# LVDS.net
KiCad netlist of a schematic drawn in Altium Designer
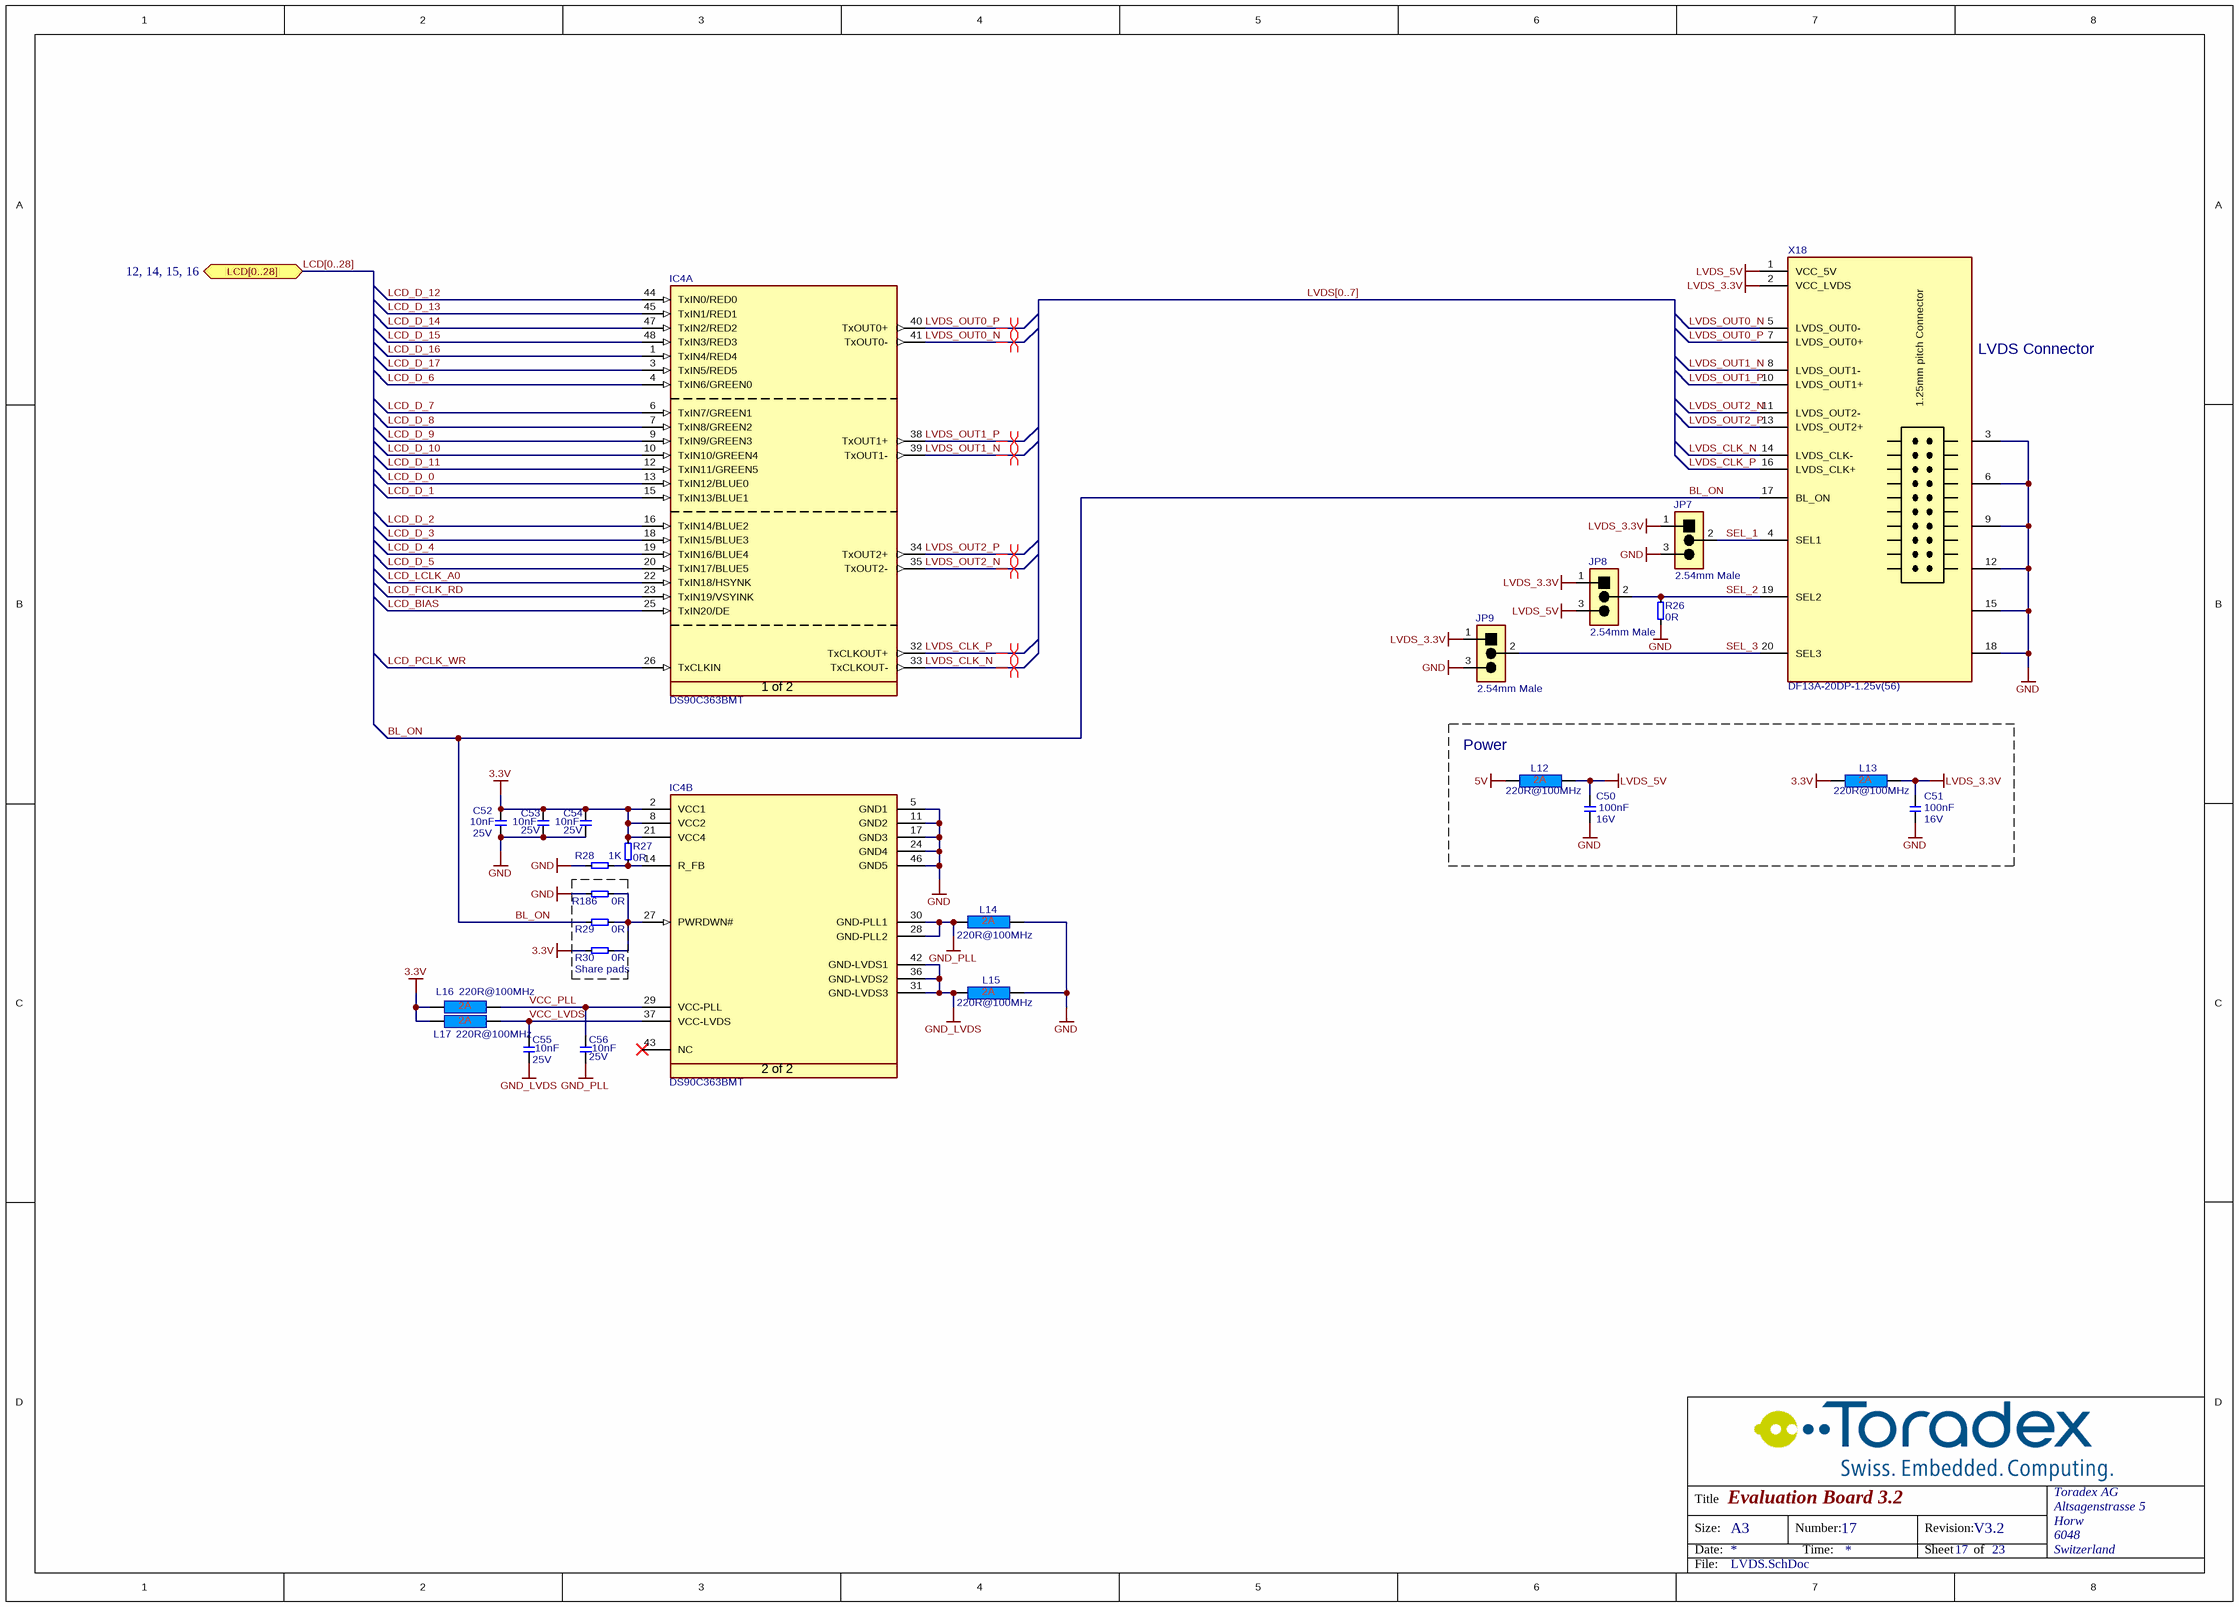
[diagram p0: LVDS.SchDoc]

(export (version "E")
  (design (tool "Eeschema 10.0.6"))
  (components
    (comp (ref "C50")
      (value "100nF")
      (footprint "T_CAPC0603X33N")
      (description "Capacitor Ceramic X7R 100nF 16V 10% 0603")
      (fields (field (name "TOLERANCE") "10%") (field (name "RATING") "16V"))
      (libsource (lib "Evaluation Board") (part "C-X7R-100nF-16V-10%-0603"))
    )
    (comp (ref "C51")
      (value "100nF")
      (footprint "T_CAPC0603X33N")
      (description "Capacitor Ceramic X7R 100nF 16V 10% 0603")
      (fields (field (name "TOLERANCE") "10%") (field (name "RATING") "16V"))
      (libsource (lib "Evaluation Board") (part "C-X7R-100nF-16V-10%-0603"))
    )
    (comp (ref "C52")
      (value "10nF")
      (footprint "T_CAPC0603X33N")
      (description "Capacitor Ceramic X7R 10nF 25V 10% 0603")
      (fields (field (name "TOLERANCE") "10%") (field (name "RATING") "25V"))
      (libsource (lib "Evaluation Board") (part "C-X7R-10nF-25V-10%-0603"))
    )
    (comp (ref "C53")
      (value "10nF")
      (footprint "T_CAPC0603X33N")
      (description "Capacitor Ceramic X7R 10nF 25V 10% 0603")
      (fields (field (name "TOLERANCE") "10%") (field (name "RATING") "25V"))
      (libsource (lib "Evaluation Board") (part "C-X7R-10nF-25V-10%-0603"))
    )
    (comp (ref "C54")
      (value "10nF")
      (footprint "T_CAPC0603X33N")
      (description "Capacitor Ceramic X7R 10nF 25V 10% 0603")
      (fields (field (name "TOLERANCE") "10%") (field (name "RATING") "25V"))
      (libsource (lib "Evaluation Board") (part "C-X7R-10nF-25V-10%-0603"))
    )
    (comp (ref "C55")
      (value "10nF")
      (footprint "T_CAPC0603X33N")
      (description "Capacitor Ceramic X7R 10nF 25V 10% 0603")
      (fields (field (name "TOLERANCE") "10%") (field (name "RATING") "25V"))
      (libsource (lib "Evaluation Board") (part "C-X7R-10nF-25V-10%-0603"))
    )
    (comp (ref "C56")
      (value "10nF")
      (footprint "T_CAPC0603X33N")
      (description "Capacitor Ceramic X7R 10nF 25V 10% 0603")
      (fields (field (name "TOLERANCE") "10%") (field (name "RATING") "25V"))
      (libsource (lib "Evaluation Board") (part "C-X7R-10nF-25V-10%-0603"))
    )
    (comp (ref "IC4")
      (value "DS90C363BMT")
      (footprint "SOP50P810X120-48N")
      (description "LVDS Converter")
      (fields (field (name "MANUFACTURER PART NO.") "DS90C363BMT"))
      (libsource (lib "Evaluation Board") (part "IC-NS-DS90C363BMT"))
    )
    (comp (ref "JP7")
      (value "826936-3")
      (footprint "T_TYCO_826936-3")
      (description "Jumper, 3-Pin")
      (libsource (lib "Evaluation Board") (part "CON-Tyco-826936-3-1X3-2.54mm-JP"))
    )
    (comp (ref "JP8")
      (value "826936-3")
      (footprint "T_TYCO_826936-3")
      (description "Jumper, 3-Pin")
      (libsource (lib "Evaluation Board") (part "CON-Tyco-826936-3-1X3-2.54mm-JP"))
    )
    (comp (ref "JP9")
      (value "826936-3")
      (footprint "T_TYCO_826936-3")
      (description "Jumper, 3-Pin")
      (libsource (lib "Evaluation Board") (part "CON-Tyco-826936-3-1X3-2.54mm-JP"))
    )
    (comp (ref "L12")
      (value "220R@100MHz")
      (footprint "INDC1608X95N")
      (description "220R@100MHz 2A EMI FILTER")
      (fields (field (name "TOLERANCE") "25%"))
      (libsource (lib "Evaluation Board") (part "L-220R@100MHz-2A-25%-0603"))
    )
    (comp (ref "L13")
      (value "220R@100MHz")
      (footprint "INDC1608X95N")
      (description "220R@100MHz 2A EMI FILTER")
      (fields (field (name "TOLERANCE") "25%"))
      (libsource (lib "Evaluation Board") (part "L-220R@100MHz-2A-25%-0603"))
    )
    (comp (ref "L14")
      (value "220R@100MHz")
      (footprint "INDC1608X95N")
      (description "220R@100MHz 2A EMI FILTER")
      (fields (field (name "TOLERANCE") "25%"))
      (libsource (lib "Evaluation Board") (part "L-220R@100MHz-2A-25%-0603"))
    )
    (comp (ref "L15")
      (value "220R@100MHz")
      (footprint "INDC1608X95N")
      (description "220R@100MHz 2A EMI FILTER")
      (fields (field (name "TOLERANCE") "25%"))
      (libsource (lib "Evaluation Board") (part "L-220R@100MHz-2A-25%-0603"))
    )
    (comp (ref "L16")
      (value "220R@100MHz")
      (footprint "INDC1608X95N")
      (description "220R@100MHz 2A EMI FILTER")
      (fields (field (name "TOLERANCE") "25%"))
      (libsource (lib "Evaluation Board") (part "L-220R@100MHz-2A-25%-0603"))
    )
    (comp (ref "L17")
      (value "220R@100MHz")
      (footprint "INDC1608X95N")
      (description "220R@100MHz 2A EMI FILTER")
      (fields (field (name "TOLERANCE") "25%"))
      (libsource (lib "Evaluation Board") (part "L-220R@100MHz-2A-25%-0603"))
    )
    (comp (ref "R26")
      (value "0R")
      (footprint "t_RESC0603X30N")
      (description "Resistor 0 ohm 63mW 1% 0603")
      (fields (field (name "TOLERANCE") "1%"))
      (libsource (lib "Evaluation Board") (part "R-0R-63mW-1%-0603"))
    )
    (comp (ref "R27")
      (value "0R")
      (footprint "t_RESC0603X30N")
      (description "Resistor 0 ohm 63mW 1% 0603")
      (fields (field (name "TOLERANCE") "1%"))
      (libsource (lib "Evaluation Board") (part "R-0R-63mW-1%-0603"))
    )
    (comp (ref "R28")
      (value "1K")
      (footprint "t_RESC0603X30N")
      (description "Resistor 1 Kohm 63mW 5% 0603")
      (fields (field (name "TOLERANCE") "5%"))
      (libsource (lib "Evaluation Board") (part "R-1KR-63mW-5%-0603"))
    )
    (comp (ref "R29")
      (value "0R")
      (footprint "t_RESC0603X30N")
      (description "Resistor 0 ohm 63mW 1% 0603")
      (fields (field (name "TOLERANCE") "1%"))
      (libsource (lib "Evaluation Board") (part "R-0R-63mW-1%-0603"))
    )
    (comp (ref "R30")
      (value "0R")
      (footprint "t_RESC0603X30N")
      (description "Resistor 0 ohm 63mW 1% 0603")
      (fields (field (name "TOLERANCE") "1%"))
      (libsource (lib "Evaluation Board") (part "R-0R-63mW-1%-0603"))
    )
    (comp (ref "R186")
      (value "0R")
      (footprint "t_RESC0603X30N")
      (description "Resistor 0 ohm 63mW 1% 0603")
      (fields (field (name "TOLERANCE") "1%"))
      (libsource (lib "Evaluation Board") (part "R-0R-63mW-1%-0603"))
    )
    (comp (ref "X18")
      (value "CON-Hirose-DF13A-20DP-1.25v(56)-2x10-1mm")
      (footprint "T_HIROSE_DF13A-20DP-1.25V(56)")
      (description "LVDS Connector")
      (fields (field (name "MANUFACTURER PART NO.") "DF13A-20DP-1.25v(56)"))
      (libsource (lib "Evaluation Board") (part "CON-Hirose-DF13A-20DP-1.25v(56)-2x10-1mm"))
    )
  )
  (nets
    (net (code "38") (name "/BL_ON") (class "Default")
      (node (ref "R29") (pin "1") (pinfunction "1_1") (pintype "passive"))
      (node (ref "X18") (pin "17") (pinfunction "BL_ON_17") (pintype "passive"))
    )
    (net (code "40") (name "/LCD_BIAS") (class "Default")
      (node (ref "IC4") (pin "25") (pinfunction "TxIN20/DE_25") (pintype "input"))
    )
    (net (code "41") (name "/LCD_D_0") (class "Default")
      (node (ref "IC4") (pin "13") (pinfunction "TxIN12/BLUE0_13") (pintype "input"))
    )
    (net (code "42") (name "/LCD_D_1") (class "Default")
      (node (ref "IC4") (pin "15") (pinfunction "TxIN13/BLUE1_15") (pintype "input"))
    )
    (net (code "43") (name "/LCD_D_2") (class "Default")
      (node (ref "IC4") (pin "16") (pinfunction "TxIN14/BLUE2_16") (pintype "input"))
    )
    (net (code "44") (name "/LCD_D_3") (class "Default")
      (node (ref "IC4") (pin "18") (pinfunction "TxIN15/BLUE3_18") (pintype "input"))
    )
    (net (code "45") (name "/LCD_D_4") (class "Default")
      (node (ref "IC4") (pin "19") (pinfunction "TxIN16/BLUE4_19") (pintype "input"))
    )
    (net (code "46") (name "/LCD_D_5") (class "Default")
      (node (ref "IC4") (pin "20") (pinfunction "TxIN17/BLUE5_20") (pintype "input"))
    )
    (net (code "47") (name "/LCD_D_6") (class "Default")
      (node (ref "IC4") (pin "4") (pinfunction "TxIN6/GREEN0_4") (pintype "input"))
    )
    (net (code "48") (name "/LCD_D_7") (class "Default")
      (node (ref "IC4") (pin "6") (pinfunction "TxIN7/GREEN1_6") (pintype "input"))
    )
    (net (code "49") (name "/LCD_D_8") (class "Default")
      (node (ref "IC4") (pin "7") (pinfunction "TxIN8/GREEN2_7") (pintype "input"))
    )
    (net (code "50") (name "/LCD_D_9") (class "Default")
      (node (ref "IC4") (pin "9") (pinfunction "TxIN9/GREEN3_9") (pintype "input"))
    )
    (net (code "51") (name "/LCD_D_10") (class "Default")
      (node (ref "IC4") (pin "10") (pinfunction "TxIN10/GREEN4_10") (pintype "input"))
    )
    (net (code "52") (name "/LCD_D_11") (class "Default")
      (node (ref "IC4") (pin "12") (pinfunction "TxIN11/GREEN5_12") (pintype "input"))
    )
    (net (code "53") (name "/LCD_D_12") (class "Default")
      (node (ref "IC4") (pin "44") (pinfunction "TxIN0/RED0_44") (pintype "input"))
    )
    (net (code "54") (name "/LCD_D_13") (class "Default")
      (node (ref "IC4") (pin "45") (pinfunction "TxIN1/RED1_45") (pintype "input"))
    )
    (net (code "55") (name "/LCD_D_14") (class "Default")
      (node (ref "IC4") (pin "47") (pinfunction "TxIN2/RED2_47") (pintype "input"))
    )
    (net (code "56") (name "/LCD_D_15") (class "Default")
      (node (ref "IC4") (pin "48") (pinfunction "TxIN3/RED3_48") (pintype "input"))
    )
    (net (code "57") (name "/LCD_D_16") (class "Default")
      (node (ref "IC4") (pin "1") (pinfunction "TxIN4/RED4_1") (pintype "input"))
    )
    (net (code "58") (name "/LCD_D_17") (class "Default")
      (node (ref "IC4") (pin "3") (pinfunction "TxIN5/RED5_3") (pintype "input"))
    )
    (net (code "59") (name "/LCD_FCLK_RD") (class "Default")
      (node (ref "IC4") (pin "23") (pinfunction "TxIN19/VSYINK_23") (pintype "input"))
    )
    (net (code "60") (name "/LCD_LCLK_A0") (class "Default")
      (node (ref "IC4") (pin "22") (pinfunction "TxIN18/HSYNK_22") (pintype "input"))
    )
    (net (code "61") (name "/LCD_PCLK_WR") (class "Default")
      (node (ref "IC4") (pin "26") (pinfunction "TxCLKIN_26") (pintype "input"))
    )
    (net (code "63") (name "/LVDS_CLK_N") (class "Default")
      (node (ref "IC4") (pin "33") (pinfunction "TxCLKOUT-_33") (pintype "output"))
      (node (ref "X18") (pin "14") (pinfunction "LVDS_CLK-_14") (pintype "passive"))
    )
    (net (code "64") (name "/LVDS_CLK_P") (class "Default")
      (node (ref "IC4") (pin "32") (pinfunction "TxCLKOUT+_32") (pintype "output"))
      (node (ref "X18") (pin "16") (pinfunction "LVDS_CLK+_16") (pintype "passive"))
    )
    (net (code "65") (name "/LVDS_OUT0_N") (class "Default")
      (node (ref "IC4") (pin "41") (pinfunction "TxOUT0-_41") (pintype "output"))
      (node (ref "X18") (pin "5") (pinfunction "LVDS_OUT0-_5") (pintype "passive"))
    )
    (net (code "66") (name "/LVDS_OUT0_P") (class "Default")
      (node (ref "IC4") (pin "40") (pinfunction "TxOUT0+_40") (pintype "output"))
      (node (ref "X18") (pin "7") (pinfunction "LVDS_OUT0+_7") (pintype "passive"))
    )
    (net (code "67") (name "/LVDS_OUT1_N") (class "Default")
      (node (ref "IC4") (pin "39") (pinfunction "TxOUT1-_39") (pintype "output"))
      (node (ref "X18") (pin "8") (pinfunction "LVDS_OUT1-_8") (pintype "passive"))
    )
    (net (code "68") (name "/LVDS_OUT1_P") (class "Default")
      (node (ref "IC4") (pin "38") (pinfunction "TxOUT1+_38") (pintype "output"))
      (node (ref "X18") (pin "10") (pinfunction "LVDS_OUT1+_10") (pintype "passive"))
    )
    (net (code "69") (name "/LVDS_OUT2_N") (class "Default")
      (node (ref "IC4") (pin "35") (pinfunction "TxOUT2-_35") (pintype "output"))
      (node (ref "X18") (pin "11") (pinfunction "LVDS_OUT2-_11") (pintype "passive"))
    )
    (net (code "70") (name "/LVDS_OUT2_P") (class "Default")
      (node (ref "IC4") (pin "34") (pinfunction "TxOUT2+_34") (pintype "output"))
      (node (ref "X18") (pin "13") (pinfunction "LVDS_OUT2+_13") (pintype "passive"))
    )
    (net (code "71") (name "/SEL_1") (class "Default")
      (node (ref "JP7") (pin "2") (pinfunction "2_2") (pintype "passive"))
      (node (ref "X18") (pin "4") (pinfunction "SEL1_4") (pintype "passive"))
    )
    (net (code "72") (name "/SEL_2") (class "Default")
      (node (ref "JP8") (pin "2") (pinfunction "2_2") (pintype "passive"))
      (node (ref "R26") (pin "2") (pinfunction "2_2") (pintype "passive"))
      (node (ref "X18") (pin "19") (pinfunction "SEL2_19") (pintype "passive"))
    )
    (net (code "73") (name "/SEL_3") (class "Default")
      (node (ref "JP9") (pin "2") (pinfunction "2_2") (pintype "passive"))
      (node (ref "X18") (pin "20") (pinfunction "SEL3_20") (pintype "passive"))
    )
    (net (code "74") (name "/VCC_LVDS") (class "Default")
      (node (ref "C55") (pin "2") (pinfunction "2_2") (pintype "passive"))
      (node (ref "IC4") (pin "37") (pinfunction "VCC-LVDS_37") (pintype "power_in"))
      (node (ref "L17") (pin "2") (pinfunction "2_2") (pintype "passive"))
    )
    (net (code "75") (name "/VCC_PLL") (class "Default")
      (node (ref "C56") (pin "2") (pinfunction "2_2") (pintype "passive"))
      (node (ref "IC4") (pin "29") (pinfunction "VCC-PLL_29") (pintype "power_in"))
      (node (ref "L16") (pin "2") (pinfunction "2_2") (pintype "passive"))
    )
    (net (code "76") (name "3.3V") (class "Default")
      (node (ref "C52") (pin "2") (pinfunction "2_2") (pintype "passive"))
      (node (ref "C53") (pin "2") (pinfunction "2_2") (pintype "passive"))
      (node (ref "C54") (pin "2") (pinfunction "2_2") (pintype "passive"))
      (node (ref "IC4") (pin "2") (pinfunction "VCC1_2") (pintype "power_in"))
      (node (ref "IC4") (pin "21") (pinfunction "VCC4_21") (pintype "power_in"))
      (node (ref "IC4") (pin "8") (pinfunction "VCC2_8") (pintype "power_in"))
      (node (ref "L13") (pin "1") (pinfunction "1_1") (pintype "passive"))
      (node (ref "L16") (pin "1") (pinfunction "1_1") (pintype "passive"))
      (node (ref "L17") (pin "1") (pinfunction "1_1") (pintype "passive"))
      (node (ref "R27") (pin "2") (pinfunction "2_2") (pintype "passive"))
      (node (ref "R30") (pin "1") (pinfunction "1_1") (pintype "passive"))
    )
    (net (code "77") (name "5V") (class "Default")
      (node (ref "L12") (pin "1") (pinfunction "1_1") (pintype "passive"))
    )
    (net (code "78") (name "GND") (class "Default")
      (node (ref "C50") (pin "1") (pinfunction "1_1") (pintype "passive"))
      (node (ref "C51") (pin "1") (pinfunction "1_1") (pintype "passive"))
      (node (ref "C52") (pin "1") (pinfunction "1_1") (pintype "passive"))
      (node (ref "C53") (pin "1") (pinfunction "1_1") (pintype "passive"))
      (node (ref "C54") (pin "1") (pinfunction "1_1") (pintype "passive"))
      (node (ref "IC4") (pin "11") (pinfunction "GND2_11") (pintype "power_in"))
      (node (ref "IC4") (pin "17") (pinfunction "GND3_17") (pintype "power_in"))
      (node (ref "IC4") (pin "24") (pinfunction "GND4_24") (pintype "power_in"))
      (node (ref "IC4") (pin "46") (pinfunction "GND5_46") (pintype "power_in"))
      (node (ref "IC4") (pin "5") (pinfunction "GND1_5") (pintype "power_in"))
      (node (ref "JP7") (pin "3") (pinfunction "3_3") (pintype "passive"))
      (node (ref "JP9") (pin "3") (pinfunction "3_3") (pintype "passive"))
      (node (ref "L14") (pin "2") (pinfunction "2_2") (pintype "passive"))
      (node (ref "L15") (pin "2") (pinfunction "2_2") (pintype "passive"))
      (node (ref "R186") (pin "1") (pinfunction "1_1") (pintype "passive"))
      (node (ref "R26") (pin "1") (pinfunction "1_1") (pintype "passive"))
      (node (ref "R28") (pin "1") (pinfunction "1_1") (pintype "passive"))
      (node (ref "X18") (pin "12") (pinfunction "GND_12") (pintype "passive"))
      (node (ref "X18") (pin "15") (pinfunction "GND_15") (pintype "passive"))
      (node (ref "X18") (pin "18") (pinfunction "GND_18") (pintype "passive"))
      (node (ref "X18") (pin "3") (pinfunction "GND_3") (pintype "passive"))
      (node (ref "X18") (pin "6") (pinfunction "GND_6") (pintype "passive"))
      (node (ref "X18") (pin "9") (pinfunction "GND_9") (pintype "passive"))
    )
    (net (code "79") (name "GND_LVDS") (class "Default")
      (node (ref "C55") (pin "1") (pinfunction "1_1") (pintype "passive"))
      (node (ref "IC4") (pin "31") (pinfunction "GND-LVDS3_31") (pintype "power_in"))
      (node (ref "IC4") (pin "36") (pinfunction "GND-LVDS2_36") (pintype "power_in"))
      (node (ref "IC4") (pin "42") (pinfunction "GND-LVDS1_42") (pintype "power_in"))
      (node (ref "L15") (pin "1") (pinfunction "1_1") (pintype "passive"))
    )
    (net (code "80") (name "GND_PLL") (class "Default")
      (node (ref "C56") (pin "1") (pinfunction "1_1") (pintype "passive"))
      (node (ref "IC4") (pin "28") (pinfunction "GND-PLL2_28") (pintype "power_in"))
      (node (ref "IC4") (pin "30") (pinfunction "GND-PLL1_30") (pintype "power_in"))
      (node (ref "L14") (pin "1") (pinfunction "1_1") (pintype "passive"))
    )
    (net (code "81") (name "LVDS_3.3V") (class "Default")
      (node (ref "C51") (pin "2") (pinfunction "2_2") (pintype "passive"))
      (node (ref "JP7") (pin "1") (pinfunction "1_1") (pintype "passive"))
      (node (ref "JP8") (pin "1") (pinfunction "1_1") (pintype "passive"))
      (node (ref "JP9") (pin "1") (pinfunction "1_1") (pintype "passive"))
      (node (ref "L13") (pin "2") (pinfunction "2_2") (pintype "passive"))
      (node (ref "X18") (pin "2") (pinfunction "VCC_LVDS_2") (pintype "passive"))
    )
    (net (code "82") (name "LVDS_5V") (class "Default")
      (node (ref "C50") (pin "2") (pinfunction "2_2") (pintype "passive"))
      (node (ref "JP8") (pin "3") (pinfunction "3_3") (pintype "passive"))
      (node (ref "L12") (pin "2") (pinfunction "2_2") (pintype "passive"))
      (node (ref "X18") (pin "1") (pinfunction "VCC_5V_1") (pintype "passive"))
    )
    (net (code "83") (name "Net-(IC4B-PWRDWN#)") (class "Default")
      (node (ref "IC4") (pin "27") (pinfunction "PWRDWN#_27") (pintype "input"))
      (node (ref "R186") (pin "2") (pinfunction "2_2") (pintype "passive"))
      (node (ref "R29") (pin "2") (pinfunction "2_2") (pintype "passive"))
      (node (ref "R30") (pin "2") (pinfunction "2_2") (pintype "passive"))
    )
    (net (code "84") (name "Net-(IC4B-R_FB)") (class "Default")
      (node (ref "IC4") (pin "14") (pinfunction "R_FB_14") (pintype "power_in"))
      (node (ref "R27") (pin "1") (pinfunction "1_1") (pintype "passive"))
      (node (ref "R28") (pin "2") (pinfunction "2_2") (pintype "passive"))
    )
    (net (code "85") (name "unconnected-(IC4B-NC-Pad43)") (class "Default")
      (node (ref "IC4") (pin "43") (pinfunction "NC_43") (pintype "passive+no_connect"))
    )
  )
)
